# ProDocument_RFID-ARDUINO-FABLAB-BG_2024-.net
KiCad netlist of a schematic drawn in EasyEDA Pro
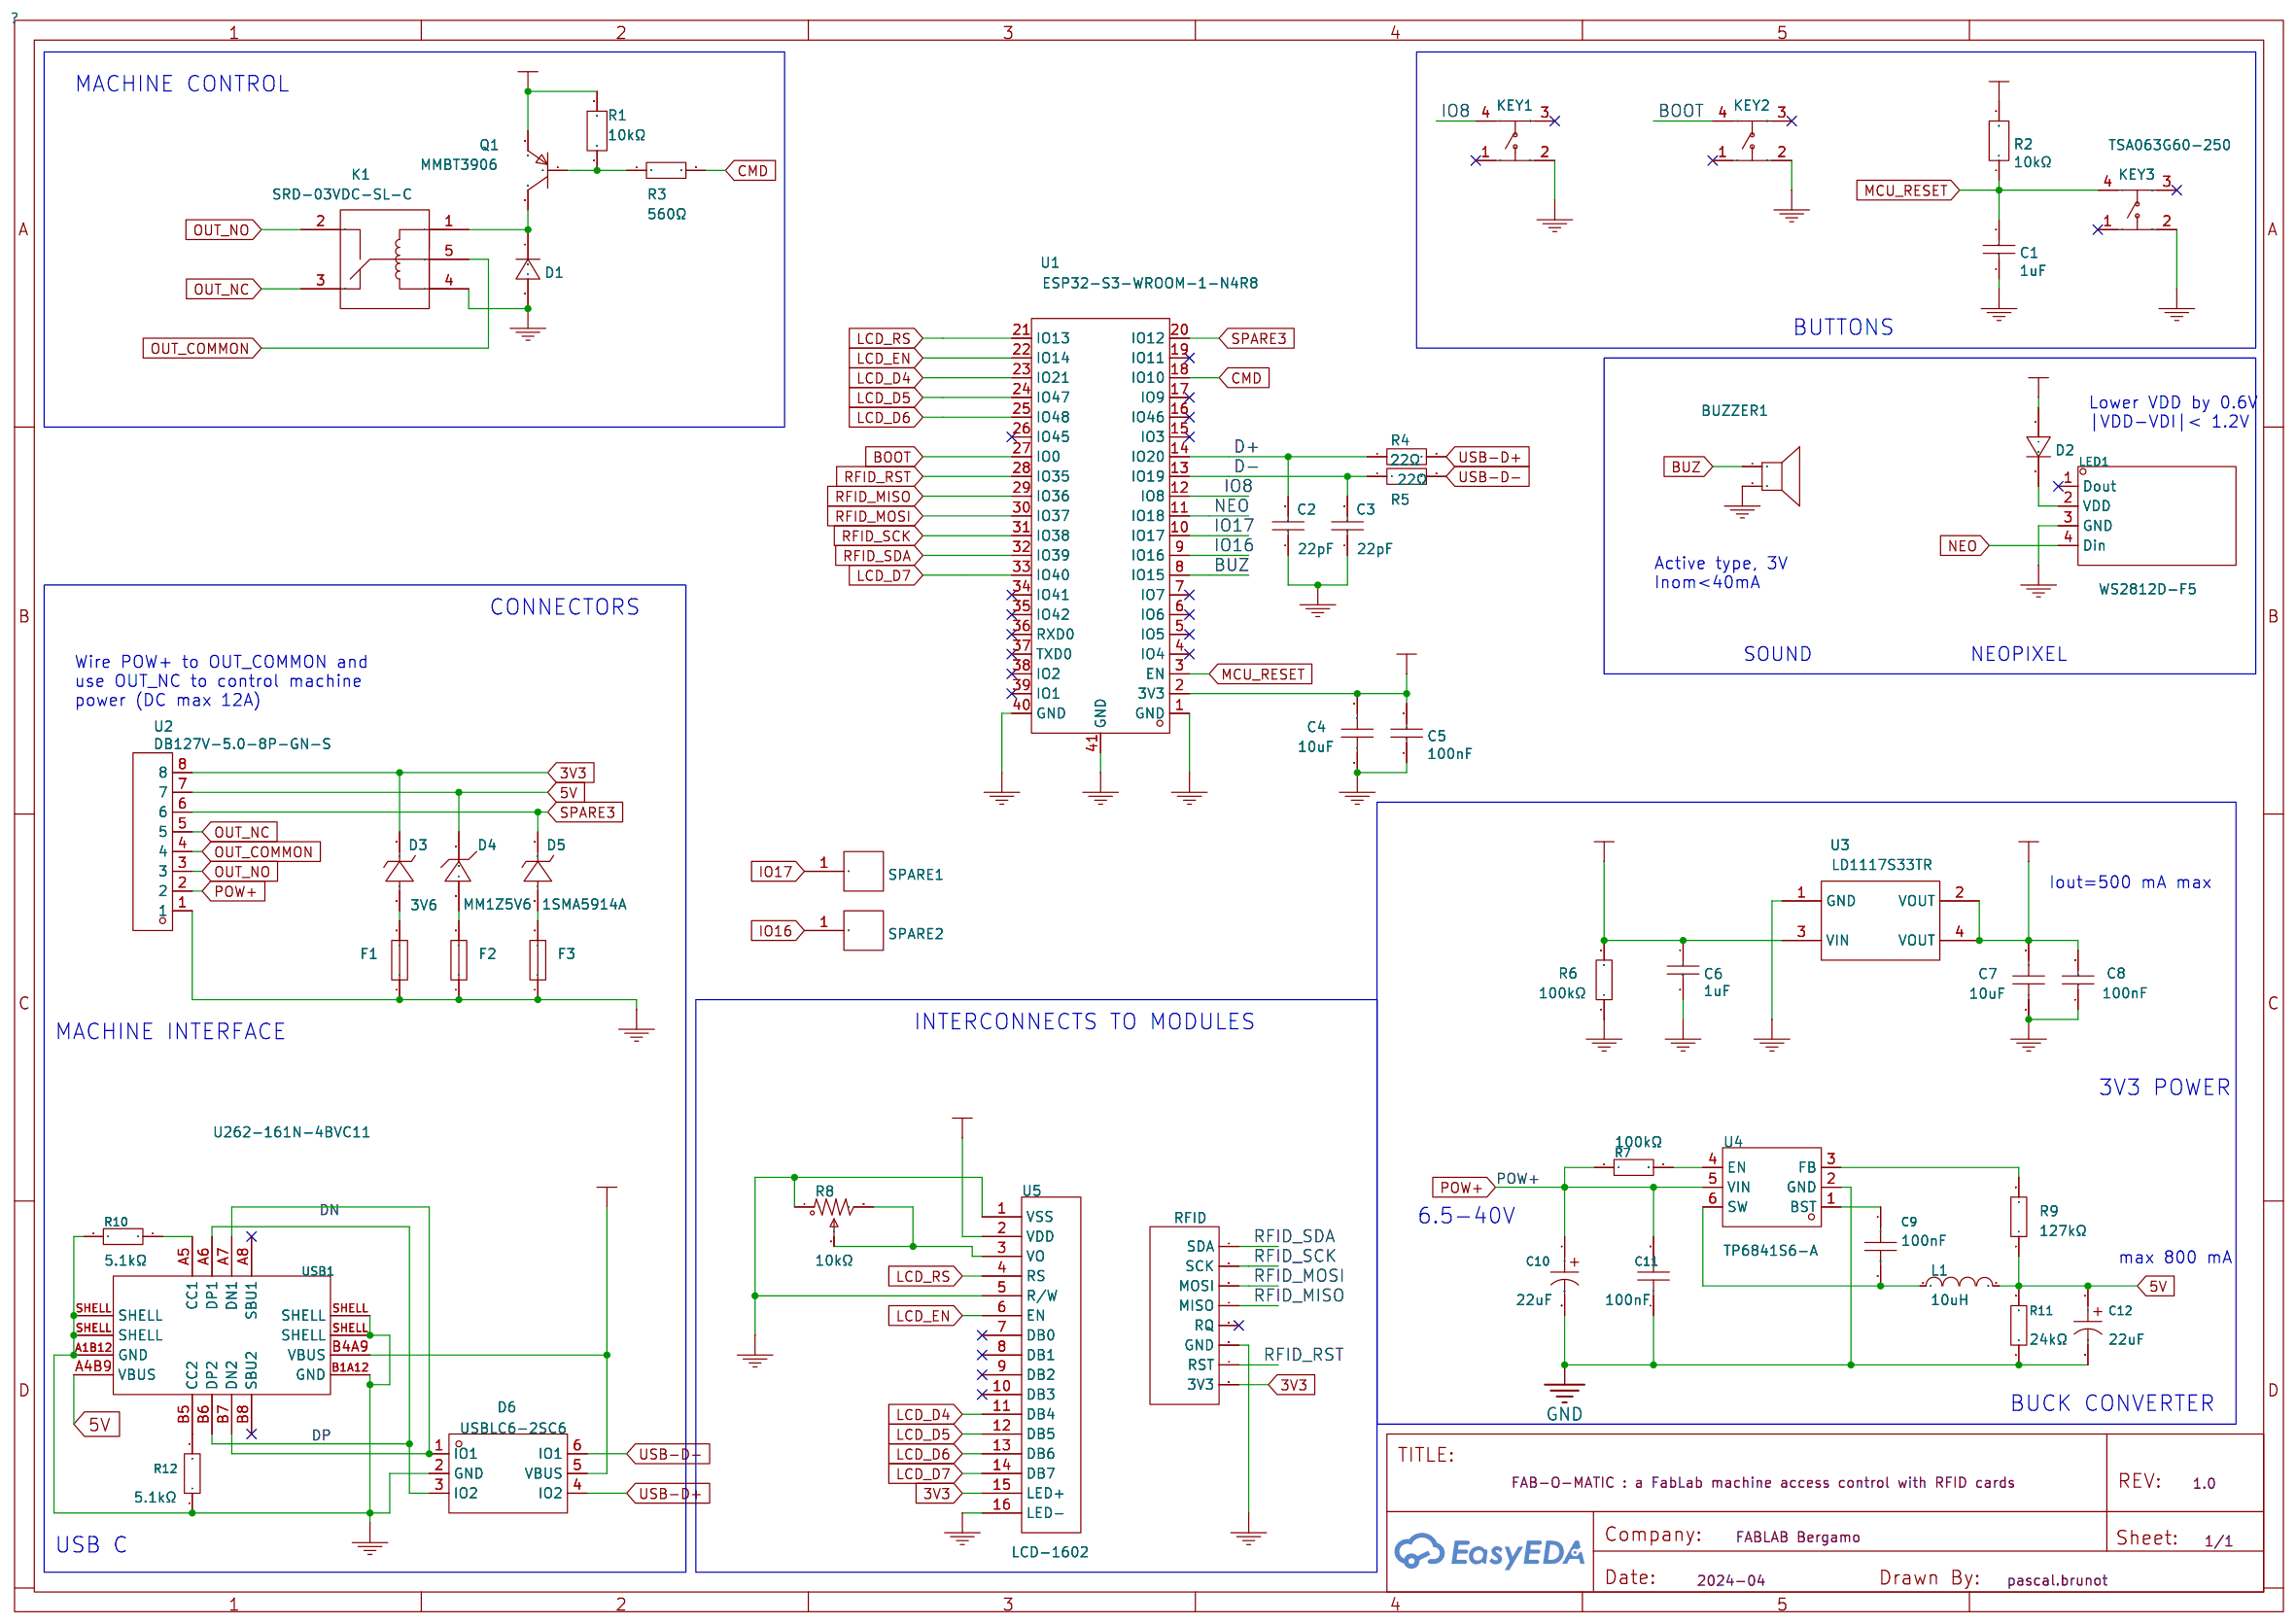
[diagram p0: schematic sheet]

(export (version "E")
  (design (tool "Eeschema 10.0.6"))
  (components
    (comp (ref "BUZZER1")
      (value "4kHz")
      (fields (field (name "Manufacturer Part") "SFN-12055PA6.5") (field (name "Manufacturer") "S&S(海旭)"))
      (libsource (lib "easyedapro") (part "4000Hz"))
    )
    (comp (ref "C1")
      (value "1uF")
      (fields
        (field (name "Manufacturer Part") "CL21B105KBFNNNE")
        (field (name "Manufacturer") "SAMSUNG(三星)")
      )
      (libsource (lib "easyedapro") (part "1uF"))
    )
    (comp (ref "C2")
      (value "22pF")
      (fields
        (field (name "Manufacturer Part") "CL10C220JB8NNNC")
        (field (name "Manufacturer") "SAMSUNG(三星)")
      )
      (libsource (lib "easyedapro") (part "22pF"))
    )
    (comp (ref "C3")
      (value "22pF")
      (fields
        (field (name "Manufacturer Part") "CL10C220JB8NNNC")
        (field (name "Manufacturer") "SAMSUNG(三星)")
      )
      (libsource (lib "easyedapro") (part "22pF"))
    )
    (comp (ref "C4")
      (value "10uF")
      (fields
        (field (name "Manufacturer Part") "GRM21BR61H106KE43L")
        (field (name "Manufacturer") "muRata(村田)")
      )
      (libsource (lib "easyedapro") (part "10uF"))
    )
    (comp (ref "C5")
      (value "100nF")
      (fields
        (field (name "Manufacturer Part") "CL21B104KCFNNNE")
        (field (name "Manufacturer") "SAMSUNG(三星)")
      )
      (libsource (lib "easyedapro") (part "100nF"))
    )
    (comp (ref "C6")
      (value "1uF")
      (fields
        (field (name "Manufacturer Part") "CL21B105KBFNNNE")
        (field (name "Manufacturer") "SAMSUNG(三星)")
      )
      (libsource (lib "easyedapro") (part "1uF"))
    )
    (comp (ref "C7")
      (value "10uF")
      (fields
        (field (name "Manufacturer Part") "GRM21BR61H106KE43L")
        (field (name "Manufacturer") "muRata(村田)")
      )
      (libsource (lib "easyedapro") (part "10uF"))
    )
    (comp (ref "C8")
      (value "100nF")
      (fields
        (field (name "Manufacturer Part") "CL21B104KCFNNNE")
        (field (name "Manufacturer") "SAMSUNG(三星)")
      )
      (libsource (lib "easyedapro") (part "100nF"))
    )
    (comp (ref "C9")
      (value "100nF")
      (footprint "easyedapro:C0603")
      (fields
        (field (name "Manufacturer Part") "CC0603KRX7R9BB104")
        (field (name "Manufacturer") "YAGEO(国巨)")
      )
      (libsource (lib "easyedapro") (part "CC0603KRX7R9BB104"))
    )
    (comp (ref "C10")
      (value "22uF")
      (footprint "easyedapro:CAP-SMD_BD6.3-L6.6-W6.6-FD")
      (fields
        (field (name "Manufacturer Part") "RVT22UF50V67RV0028")
        (field (name "Manufacturer") "KNSCHA(科尼盛)")
      )
      (libsource (lib "easyedapro") (part "RVT22UF50V67RV0028"))
    )
    (comp (ref "C11")
      (value "100nF")
      (footprint "easyedapro:C0603")
      (fields
        (field (name "Manufacturer Part") "CC0603KRX7R9BB104")
        (field (name "Manufacturer") "YAGEO(国巨)")
      )
      (libsource (lib "easyedapro") (part "CC0603KRX7R9BB104"))
    )
    (comp (ref "C12")
      (value "22uF")
      (footprint "easyedapro:CAP-SMD_BD6.3-L6.6-W6.6-FD")
      (fields
        (field (name "Manufacturer Part") "RVT22UF50V67RV0028")
        (field (name "Manufacturer") "KNSCHA(科尼盛)")
      )
      (libsource (lib "easyedapro") (part "RVT22UF50V67RV0028"))
    )
    (comp (ref "D1")
      (value "SM4007PL")
      (fields (field (name "Manufacturer") "MDD"))
      (libsource (lib "easyedapro") (part "SM4007PL"))
    )
    (comp (ref "D2")
      (value "SM4007PL")
      (fields (field (name "Manufacturer") "MDD"))
      (libsource (lib "easyedapro") (part "SM4007PL"))
    )
    (comp (ref "D3")
      (value "3V6")
      (fields (field (name "Manufacturer") "LGE(鲁光)"))
      (libsource (lib "easyedapro") (part "3V6"))
    )
    (comp (ref "D4")
      (value "MM1Z5V6")
      (fields (field (name "Manufacturer") "ST(先科)"))
      (libsource (lib "easyedapro") (part "5V6"))
    )
    (comp (ref "D5")
      (value "1SMA5914A")
      (fields (field (name "Manufacturer") "LGE(鲁光)"))
      (libsource (lib "easyedapro") (part "3V6"))
    )
    (comp (ref "D6")
      (value "USBLC6-2SC6")
      (fields (field (name "Manufacturer") "TECH PUBLIC(台舟)"))
      (libsource (lib "easyedapro") (part "USBLC6"))
    )
    (comp (ref "F1")
      (value "1206L016WR")
      (fields (field (name "Manufacturer") "Littelfuse(美国力特)"))
      (libsource (lib "easyedapro") (part "1206L016WR"))
    )
    (comp (ref "F2")
      (value "1206L016WR")
      (fields (field (name "Manufacturer") "Littelfuse(美国力特)"))
      (libsource (lib "easyedapro") (part "1206L016WR"))
    )
    (comp (ref "F3")
      (value "1206L016WR")
      (fields (field (name "Manufacturer") "Littelfuse(美国力特)"))
      (libsource (lib "easyedapro") (part "1206L016WR"))
    )
    (comp (ref "K1")
      (value "SRD-03VDC-SL-C")
      (fields (field (name "Manufacturer") "松乐"))
      (libsource (lib "easyedapro") (part "SRD-03VDC-SL-C_C496430"))
    )
    (comp (ref "KEY1")
      (value "TSA063G60-250")
      (footprint "easyedapro:KEY-SMD_4P-L6.1-W6.1-P4.50-LS9.0")
      (fields (field (name "Manufacturer") "BRIGHT(博瑞泰)"))
      (libsource (lib "easyedapro") (part "TSA063G60-250"))
    )
    (comp (ref "KEY2")
      (value "TSA063G60-250")
      (footprint "easyedapro:KEY-SMD_4P-L6.1-W6.1-P4.50-LS9.0")
      (fields (field (name "Manufacturer") "BRIGHT(博瑞泰)"))
      (libsource (lib "easyedapro") (part "TSA063G60-250"))
    )
    (comp (ref "KEY3")
      (value "TSA063G60-250")
      (footprint "easyedapro:KEY-SMD_4P-L6.1-W6.1-P4.50-LS9.0")
      (fields (field (name "Manufacturer") "BRIGHT(博瑞泰)"))
      (libsource (lib "easyedapro") (part "TSA063G60-250"))
    )
    (comp (ref "L1")
      (value "10uH")
      (footprint "easyedapro:IND-SMD_L4.0-W4.0")
      (fields (field (name "Manufacturer Part") "SWPA4030S100MT") (field (name "Manufacturer") "Sunlord(顺络)"))
      (libsource (lib "easyedapro") (part "SWPA4030S100MT"))
    )
    (comp (ref "LED1")
      (value "WS2812D-F5")
      (footprint "easyedapro:LED-TH_4P-BD5.8-P1.30")
      (description "Lamp Holder Type:5mm圆形灯头")
      (fields (field (name "Manufacturer") "worldsemi"))
      (libsource (lib "easyedapro") (part "WS2812D-F5"))
    )
    (comp (ref "P1")
      (value "RFID")
      (footprint "easyedapro:footprint_17af")
      (fields
        (field (name "Manufacturer Part") "Female headerHDR1X8-2.54")
        (field (name "Manufacturer") "BOOMELE")
      )
      (libsource (lib "easyedapro") (part "RFID"))
    )
    (comp (ref "Q1")
      (value "MMBT3906")
      (fields (field (name "Manufacturer") "High Diode(海德)"))
      (libsource (lib "easyedapro") (part "2N3906-AP"))
    )
    (comp (ref "R1")
      (value "10kΩ")
      (fields
        (field (name "Manufacturer Part") "0805W8F1002T5E")
        (field (name "Manufacturer") "UNI-ROYAL(厚声)")
      )
      (libsource (lib "easyedapro") (part "10k"))
    )
    (comp (ref "R2")
      (value "10kΩ")
      (fields
        (field (name "Manufacturer Part") "0805W8F1002T5E")
        (field (name "Manufacturer") "UNI-ROYAL(厚声)")
      )
      (libsource (lib "easyedapro") (part "10k"))
    )
    (comp (ref "R3")
      (value "560Ω")
      (fields
        (field (name "Manufacturer Part") "0805W8F5600T5E")
        (field (name "Manufacturer") "UNI-ROYAL(厚声)")
      )
      (libsource (lib "easyedapro") (part "560Ω"))
    )
    (comp (ref "R4")
      (value "22Ω")
      (fields
        (field (name "Manufacturer Part") "0603WAF220JT5E")
        (field (name "Manufacturer") "UNI-ROYAL(厚声)")
      )
      (libsource (lib "easyedapro") (part "22"))
    )
    (comp (ref "R5")
      (value "22Ω")
      (fields
        (field (name "Manufacturer Part") "0603WAF220JT5E")
        (field (name "Manufacturer") "UNI-ROYAL(厚声)")
      )
      (libsource (lib "easyedapro") (part "22"))
    )
    (comp (ref "R6")
      (value "100kΩ")
      (fields
        (field (name "Manufacturer Part") "0805W8F1003T5E")
        (field (name "Manufacturer") "UNI-ROYAL(厚声)")
      )
      (libsource (lib "easyedapro") (part "100kΩ"))
    )
    (comp (ref "R7")
      (value "100kΩ")
      (footprint "easyedapro:R0603")
      (fields
        (field (name "Manufacturer Part") "0603WAF1003T5E")
        (field (name "Manufacturer") "UNI-ROYAL(厚声)")
      )
      (libsource (lib "easyedapro") (part "0603WAF1003T5E"))
    )
    (comp (ref "R8")
      (value "10kΩ")
      (footprint "easyedapro:RES-ADJ-TH_3362P")
      (description "Resistance: Tolerance:±10% Tolerance:±10%")
      (fields (field (name "Manufacturer Part") "3362P-1-103") (field (name "Manufacturer") "BOCHEN(博晨)"))
      (libsource (lib "easyedapro") (part "3362P-1-103_C118956"))
    )
    (comp (ref "R9")
      (value "127kΩ")
      (footprint "easyedapro:R0603")
      (fields (field (name "Manufacturer Part") "RC0603FR-07127KL") (field (name "Manufacturer") "YAGEO(国巨)"))
      (libsource (lib "easyedapro") (part "RC0603FR-07127KL"))
    )
    (comp (ref "R10")
      (value "5.1kΩ")
      (footprint "easyedapro:R0603")
      (fields
        (field (name "Manufacturer Part") "0603WAF5101T5E")
        (field (name "Manufacturer") "UNI-ROYAL(厚声)")
      )
      (libsource (lib "easyedapro") (part "0603WAF5101T5E"))
    )
    (comp (ref "R11")
      (value "24kΩ")
      (footprint "easyedapro:R0603")
      (fields
        (field (name "Manufacturer Part") "0603WAF2402T5E")
        (field (name "Manufacturer") "UNI-ROYAL(厚声)")
      )
      (libsource (lib "easyedapro") (part "0603WAF2402T5E"))
    )
    (comp (ref "R12")
      (value "5.1kΩ")
      (footprint "easyedapro:R0603")
      (fields
        (field (name "Manufacturer Part") "0603WAF5101T5E")
        (field (name "Manufacturer") "UNI-ROYAL(厚声)")
      )
      (libsource (lib "easyedapro") (part "0603WAF5101T5E"))
    )
    (comp (ref "SPARE1")
      (value "0577-0-43-80-21-27-10-0")
      (footprint "easyedapro:footprint_662d")
      (libsource (lib "easyedapro") (part "0577-0-43-80-21-27-10-0"))
    )
    (comp (ref "SPARE2")
      (value "0577-0-43-80-21-27-10-0")
      (footprint "easyedapro:footprint_662d")
      (libsource (lib "easyedapro") (part "0577-0-43-80-21-27-10-0"))
    )
    (comp (ref "U1")
      (value "ESP32-S3-WROOM-1-N4R8")
      (fields (field (name "Manufacturer") "ESPRESSIF(乐鑫)"))
      (libsource (lib "easyedapro") (part "ESP32-S3-WROOM-1-N4"))
    )
    (comp (ref "U2")
      (value "DB127V-5.0-8P-GN-S")
      (fields (field (name "Manufacturer") "DORABO(地博电气)"))
      (libsource (lib "easyedapro") (part "DB127V-5.0-8P-GN-S"))
    )
    (comp (ref "U3")
      (value "LD1117S33TR")
      (fields (field (name "Manufacturer") "ST(意法半导体)"))
      (libsource (lib "easyedapro") (part "LD1117S33TR"))
    )
    (comp (ref "U4")
      (value "TP6841S6-A")
      (footprint "easyedapro:SOT-23-6_L2.9-W1.6-P0.95-LS2.8-BL")
      (fields (field (name "Manufacturer") "TECH PUBLIC(台舟)"))
      (libsource (lib "easyedapro") (part "TP6841S6-A"))
    )
    (comp (ref "U5")
      (value "LCD-1602")
      (footprint "easyedapro:footprint_8a57")
      (fields (field (name "Manufacturer Part") "?"))
      (libsource (lib "easyedapro") (part "LCD-1602"))
    )
    (comp (ref "USB1")
      (value "U262-161N-4BVC11")
      (footprint "easyedapro:USB-3.1-SMD_U262-161N-4BVC11")
      (fields (field (name "Manufacturer") "XKB Connectivity(中国星坤)"))
      (libsource (lib "easyedapro") (part "U262-16XN-4BVC11"))
    )
  )
  (nets
    (net (code "1") (name "/D+") (class "Default")
      (node (ref "C2") (pin "2") (pinfunction "2_2") (pintype "input"))
      (node (ref "R4") (pin "1") (pinfunction "1_1") (pintype "input"))
      (node (ref "U1") (pin "14") (pinfunction "IO20_14") (pintype "unspecified"))
    )
    (net (code "2") (name "/D-") (class "Default")
      (node (ref "C3") (pin "2") (pinfunction "2_2") (pintype "input"))
      (node (ref "R5") (pin "1") (pinfunction "1_1") (pintype "input"))
      (node (ref "U1") (pin "13") (pinfunction "IO19_13") (pintype "unspecified"))
    )
    (net (code "3") (name "/DN") (class "Default")
      (node (ref "D6") (pin "1") (pinfunction "IO1_1") (pintype "unspecified"))
      (node (ref "USB1") (pin "A7") (pinfunction "DN1_A7") (pintype "input"))
      (node (ref "USB1") (pin "B7") (pinfunction "DN2_B7") (pintype "input"))
    )
    (net (code "4") (name "/DP") (class "Default")
      (node (ref "D6") (pin "3") (pinfunction "IO2_3") (pintype "unspecified"))
      (node (ref "USB1") (pin "A6") (pinfunction "DP1_A6") (pintype "input"))
      (node (ref "USB1") (pin "B6") (pinfunction "DP2_B6") (pintype "input"))
    )
    (net (code "5") (name "/IO8") (class "Default")
      (node (ref "KEY1") (pin "4") (pinfunction "4_4") (pintype "input"))
      (node (ref "U1") (pin "12") (pinfunction "IO8_12") (pintype "unspecified"))
    )
    (net (code "6") (name "3V3") (class "Default")
      (node (ref "C4") (pin "2") (pinfunction "2_2") (pintype "unspecified"))
      (node (ref "C5") (pin "2") (pinfunction "2_2") (pintype "input"))
      (node (ref "C7") (pin "2") (pinfunction "2_2") (pintype "unspecified"))
      (node (ref "C8") (pin "2") (pinfunction "2_2") (pintype "input"))
      (node (ref "D3") (pin "1") (pinfunction "C_1") (pintype "unspecified"))
      (node (ref "P1") (pin "8") (pinfunction "3V3_8") (pintype "input"))
      (node (ref "Q1") (pin "1") (pinfunction "1_1") (pintype "input"))
      (node (ref "R1") (pin "2") (pinfunction "2_2") (pintype "unspecified"))
      (node (ref "R2") (pin "2") (pinfunction "2_2") (pintype "unspecified"))
      (node (ref "U1") (pin "2") (pinfunction "3V3_2") (pintype "unspecified"))
      (node (ref "U2") (pin "8") (pinfunction "8_8") (pintype "unspecified"))
      (node (ref "U3") (pin "2") (pinfunction "VOUT_2") (pintype "unspecified"))
      (node (ref "U3") (pin "4") (pinfunction "VOUT_4") (pintype "unspecified"))
      (node (ref "U5") (pin "15") (pinfunction "LED+_15") (pintype "unspecified"))
    )
    (net (code "7") (name "5V") (class "Default")
      (node (ref "C12") (pin "1") (pinfunction "1_1") (pintype "input"))
      (node (ref "C6") (pin "1") (pinfunction "1_1") (pintype "input"))
      (node (ref "D2") (pin "2") (pinfunction "A_2") (pintype "unspecified"))
      (node (ref "D4") (pin "1") (pinfunction "C_1") (pintype "unspecified"))
      (node (ref "D6") (pin "5") (pinfunction "VBUS_5") (pintype "unspecified"))
      (node (ref "L1") (pin "2") (pinfunction "2_2") (pintype "input"))
      (node (ref "R11") (pin "2") (pinfunction "2_2") (pintype "input"))
      (node (ref "R6") (pin "2") (pinfunction "2_2") (pintype "unspecified"))
      (node (ref "R9") (pin "1") (pinfunction "1_1") (pintype "unspecified"))
      (node (ref "U2") (pin "7") (pinfunction "7_7") (pintype "unspecified"))
      (node (ref "U3") (pin "3") (pinfunction "VIN_3") (pintype "unspecified"))
      (node (ref "U5") (pin "2") (pinfunction "VDD_2") (pintype "unspecified"))
      (node (ref "USB1") (pin "A4B9") (pinfunction "VBUS_A4B9") (pintype "input"))
      (node (ref "USB1") (pin "B4A9") (pinfunction "VBUS_B4A9") (pintype "input"))
    )
    (net (code "8") (name "BOOT") (class "Default")
      (node (ref "KEY2") (pin "4") (pinfunction "4_4") (pintype "input"))
      (node (ref "U1") (pin "27") (pinfunction "IO0_27") (pintype "unspecified"))
    )
    (net (code "9") (name "BUZ") (class "Default")
      (node (ref "BUZZER1") (pin "1") (pinfunction "1_1") (pintype "unspecified"))
      (node (ref "U1") (pin "8") (pinfunction "IO15_8") (pintype "unspecified"))
    )
    (net (code "10") (name "CMD") (class "Default")
      (node (ref "R3") (pin "2") (pinfunction "2_2") (pintype "input"))
      (node (ref "U1") (pin "18") (pinfunction "IO10_18") (pintype "unspecified"))
    )
    (net (code "11") (name "GND") (class "Default")
      (node (ref "BUZZER1") (pin "2") (pinfunction "2_2") (pintype "unspecified"))
      (node (ref "C1") (pin "1") (pinfunction "1_1") (pintype "input"))
      (node (ref "C10") (pin "2") (pinfunction "2_2") (pintype "input"))
      (node (ref "C11") (pin "1") (pinfunction "1_1") (pintype "input"))
      (node (ref "C12") (pin "2") (pinfunction "2_2") (pintype "input"))
      (node (ref "C2") (pin "1") (pinfunction "1_1") (pintype "input"))
      (node (ref "C3") (pin "1") (pinfunction "1_1") (pintype "input"))
      (node (ref "C4") (pin "1") (pinfunction "1_1") (pintype "unspecified"))
      (node (ref "C5") (pin "1") (pinfunction "1_1") (pintype "input"))
      (node (ref "C6") (pin "2") (pinfunction "2_2") (pintype "input"))
      (node (ref "C7") (pin "1") (pinfunction "1_1") (pintype "unspecified"))
      (node (ref "C8") (pin "1") (pinfunction "1_1") (pintype "input"))
      (node (ref "D1") (pin "2") (pinfunction "A_2") (pintype "unspecified"))
      (node (ref "D6") (pin "2") (pinfunction "GND_2") (pintype "unspecified"))
      (node (ref "F1") (pin "1") (pinfunction "1_1") (pintype "unspecified"))
      (node (ref "F2") (pin "1") (pinfunction "1_1") (pintype "unspecified"))
      (node (ref "F3") (pin "1") (pinfunction "1_1") (pintype "unspecified"))
      (node (ref "K1") (pin "4") (pinfunction "4_4") (pintype "unspecified"))
      (node (ref "KEY1") (pin "2") (pinfunction "2_2") (pintype "input"))
      (node (ref "KEY2") (pin "2") (pinfunction "2_2") (pintype "input"))
      (node (ref "KEY3") (pin "2") (pinfunction "2_2") (pintype "input"))
      (node (ref "LED1") (pin "3") (pinfunction "GND_3") (pintype "input"))
      (node (ref "P1") (pin "6") (pinfunction "GND_6") (pintype "input"))
      (node (ref "R10") (pin "2") (pinfunction "2_2") (pintype "input"))
      (node (ref "R11") (pin "1") (pinfunction "1_1") (pintype "input"))
      (node (ref "R12") (pin "1") (pinfunction "1_1") (pintype "input"))
      (node (ref "R6") (pin "1") (pinfunction "1_1") (pintype "unspecified"))
      (node (ref "R8") (pin "1") (pinfunction "1_1") (pintype "input"))
      (node (ref "U1") (pin "1") (pinfunction "GND_1") (pintype "unspecified"))
      (node (ref "U1") (pin "40") (pinfunction "GND_40") (pintype "unspecified"))
      (node (ref "U1") (pin "41") (pinfunction "GND_41") (pintype "unspecified"))
      (node (ref "U2") (pin "1") (pinfunction "1_1") (pintype "unspecified"))
      (node (ref "U3") (pin "1") (pinfunction "GND_1") (pintype "unspecified"))
      (node (ref "U4") (pin "2") (pinfunction "GND_2") (pintype "input"))
      (node (ref "U5") (pin "1") (pinfunction "VSS_1") (pintype "unspecified"))
      (node (ref "U5") (pin "16") (pinfunction "LED-_16") (pintype "unspecified"))
      (node (ref "U5") (pin "5") (pinfunction "R/W_5") (pintype "unspecified"))
      (node (ref "USB1") (pin "A1B12") (pinfunction "GND_A1B12") (pintype "input"))
      (node (ref "USB1") (pin "B1A12") (pinfunction "GND_B1A12") (pintype "input"))
      (node (ref "USB1") (pin "SHELL") (pinfunction "SHELL_SHELL") (pintype "input"))
    )
    (net (code "12") (name "IO16") (class "Default")
      (node (ref "SPARE2") (pin "1") (pinfunction "1_1") (pintype "unspecified"))
      (node (ref "U1") (pin "9") (pinfunction "IO16_9") (pintype "unspecified"))
    )
    (net (code "13") (name "IO17") (class "Default")
      (node (ref "SPARE1") (pin "1") (pinfunction "1_1") (pintype "unspecified"))
      (node (ref "U1") (pin "10") (pinfunction "IO17_10") (pintype "unspecified"))
    )
    (net (code "14") (name "LCD_D4") (class "Default")
      (node (ref "U1") (pin "23") (pinfunction "IO21_23") (pintype "unspecified"))
      (node (ref "U5") (pin "11") (pinfunction "DB4_11") (pintype "unspecified"))
    )
    (net (code "15") (name "LCD_D5") (class "Default")
      (node (ref "U1") (pin "24") (pinfunction "IO47_24") (pintype "unspecified"))
      (node (ref "U5") (pin "12") (pinfunction "DB5_12") (pintype "unspecified"))
    )
    (net (code "16") (name "LCD_D6") (class "Default")
      (node (ref "U1") (pin "25") (pinfunction "IO48_25") (pintype "unspecified"))
      (node (ref "U5") (pin "13") (pinfunction "DB6_13") (pintype "unspecified"))
    )
    (net (code "17") (name "LCD_D7") (class "Default")
      (node (ref "U1") (pin "33") (pinfunction "IO40_33") (pintype "unspecified"))
      (node (ref "U5") (pin "14") (pinfunction "DB7_14") (pintype "unspecified"))
    )
    (net (code "18") (name "LCD_EN") (class "Default")
      (node (ref "U1") (pin "22") (pinfunction "IO14_22") (pintype "unspecified"))
      (node (ref "U5") (pin "6") (pinfunction "EN_6") (pintype "unspecified"))
    )
    (net (code "19") (name "LCD_RS") (class "Default")
      (node (ref "U1") (pin "21") (pinfunction "IO13_21") (pintype "unspecified"))
      (node (ref "U5") (pin "4") (pinfunction "RS_4") (pintype "unspecified"))
    )
    (net (code "20") (name "MCU_RESET") (class "Default")
      (node (ref "C1") (pin "2") (pinfunction "2_2") (pintype "input"))
      (node (ref "KEY3") (pin "4") (pinfunction "4_4") (pintype "input"))
      (node (ref "R2") (pin "1") (pinfunction "1_1") (pintype "unspecified"))
      (node (ref "U1") (pin "3") (pinfunction "EN_3") (pintype "unspecified"))
    )
    (net (code "21") (name "NEO") (class "Default")
      (node (ref "LED1") (pin "4") (pinfunction "Din_4") (pintype "input"))
      (node (ref "U1") (pin "11") (pinfunction "IO18_11") (pintype "unspecified"))
    )
    (net (code "22") (name "Net-(D1-C)") (class "Default")
      (node (ref "D1") (pin "1") (pinfunction "C_1") (pintype "unspecified"))
      (node (ref "K1") (pin "1") (pinfunction "1_1") (pintype "unspecified"))
      (node (ref "Q1") (pin "3") (pinfunction "3_3") (pintype "input"))
    )
    (net (code "23") (name "Net-(D2-C)") (class "Default")
      (node (ref "D2") (pin "1") (pinfunction "C_1") (pintype "unspecified"))
      (node (ref "LED1") (pin "2") (pinfunction "VDD_2") (pintype "input"))
    )
    (net (code "24") (name "Net-(D3-A)") (class "Default")
      (node (ref "D3") (pin "2") (pinfunction "A_2") (pintype "unspecified"))
      (node (ref "F1") (pin "2") (pinfunction "2_2") (pintype "unspecified"))
    )
    (net (code "25") (name "Net-(D4-A)") (class "Default")
      (node (ref "D4") (pin "2") (pinfunction "A_2") (pintype "unspecified"))
      (node (ref "F2") (pin "2") (pinfunction "2_2") (pintype "unspecified"))
    )
    (net (code "26") (name "Net-(D5-A)") (class "Default")
      (node (ref "D5") (pin "2") (pinfunction "A_2") (pintype "unspecified"))
      (node (ref "F3") (pin "2") (pinfunction "2_2") (pintype "unspecified"))
    )
    (net (code "27") (name "Net-(Q1-Pad2)") (class "Default")
      (node (ref "Q1") (pin "2") (pinfunction "2_2") (pintype "input"))
      (node (ref "R1") (pin "1") (pinfunction "1_1") (pintype "unspecified"))
      (node (ref "R3") (pin "1") (pinfunction "1_1") (pintype "input"))
    )
    (net (code "28") (name "Net-(U4-BST)") (class "Default")
      (node (ref "C9") (pin "1") (pinfunction "1_1") (pintype "input"))
      (node (ref "U4") (pin "1") (pinfunction "BST_1") (pintype "input"))
    )
    (net (code "29") (name "Net-(U4-EN)") (class "Default")
      (node (ref "R7") (pin "2") (pinfunction "2_2") (pintype "input"))
      (node (ref "U4") (pin "4") (pinfunction "EN_4") (pintype "input"))
    )
    (net (code "30") (name "Net-(U4-FB)") (class "Default")
      (node (ref "R9") (pin "2") (pinfunction "2_2") (pintype "unspecified"))
      (node (ref "U4") (pin "3") (pinfunction "FB_3") (pintype "input"))
    )
    (net (code "31") (name "Net-(U4-SW)") (class "Default")
      (node (ref "C9") (pin "2") (pinfunction "2_2") (pintype "input"))
      (node (ref "L1") (pin "1") (pinfunction "1_1") (pintype "input"))
      (node (ref "U4") (pin "6") (pinfunction "SW_6") (pintype "input"))
    )
    (net (code "32") (name "Net-(U5-VO)") (class "Default")
      (node (ref "R8") (pin "2") (pinfunction "2_2") (pintype "input"))
      (node (ref "R8") (pin "3") (pinfunction "3_3") (pintype "input"))
      (node (ref "U5") (pin "3") (pinfunction "VO_3") (pintype "unspecified"))
    )
    (net (code "33") (name "Net-(USB1-CC1)") (class "Default")
      (node (ref "R10") (pin "1") (pinfunction "1_1") (pintype "input"))
      (node (ref "USB1") (pin "A5") (pinfunction "CC1_A5") (pintype "input"))
    )
    (net (code "34") (name "Net-(USB1-CC2)") (class "Default")
      (node (ref "R12") (pin "2") (pinfunction "2_2") (pintype "input"))
      (node (ref "USB1") (pin "B5") (pinfunction "CC2_B5") (pintype "input"))
    )
    (net (code "35") (name "OUT_COMMON") (class "Default")
      (node (ref "K1") (pin "5") (pinfunction "5_5") (pintype "unspecified"))
      (node (ref "U2") (pin "4") (pinfunction "4_4") (pintype "unspecified"))
    )
    (net (code "36") (name "OUT_NC") (class "Default")
      (node (ref "K1") (pin "3") (pinfunction "3_3") (pintype "unspecified"))
      (node (ref "U2") (pin "5") (pinfunction "5_5") (pintype "unspecified"))
    )
    (net (code "37") (name "OUT_NO") (class "Default")
      (node (ref "K1") (pin "2") (pinfunction "2_2") (pintype "unspecified"))
      (node (ref "U2") (pin "3") (pinfunction "3_3") (pintype "unspecified"))
    )
    (net (code "38") (name "POW+") (class "Default")
      (node (ref "C10") (pin "1") (pinfunction "1_1") (pintype "input"))
      (node (ref "C11") (pin "2") (pinfunction "2_2") (pintype "input"))
      (node (ref "R7") (pin "1") (pinfunction "1_1") (pintype "input"))
      (node (ref "U2") (pin "2") (pinfunction "2_2") (pintype "unspecified"))
      (node (ref "U4") (pin "5") (pinfunction "VIN_5") (pintype "input"))
    )
    (net (code "39") (name "RFID_MISO") (class "Default")
      (node (ref "P1") (pin "4") (pinfunction "MISO_4") (pintype "input"))
      (node (ref "U1") (pin "29") (pinfunction "IO36_29") (pintype "unspecified"))
    )
    (net (code "40") (name "RFID_MOSI") (class "Default")
      (node (ref "P1") (pin "3") (pinfunction "MOSI_3") (pintype "input"))
      (node (ref "U1") (pin "30") (pinfunction "IO37_30") (pintype "unspecified"))
    )
    (net (code "41") (name "RFID_RST") (class "Default")
      (node (ref "P1") (pin "7") (pinfunction "RST_7") (pintype "input"))
      (node (ref "U1") (pin "28") (pinfunction "IO35_28") (pintype "unspecified"))
    )
    (net (code "42") (name "RFID_SCK") (class "Default")
      (node (ref "P1") (pin "2") (pinfunction "SCK_2") (pintype "input"))
      (node (ref "U1") (pin "31") (pinfunction "IO38_31") (pintype "unspecified"))
    )
    (net (code "43") (name "RFID_SDA") (class "Default")
      (node (ref "P1") (pin "1") (pinfunction "SDA_1") (pintype "input"))
      (node (ref "U1") (pin "32") (pinfunction "IO39_32") (pintype "unspecified"))
    )
    (net (code "44") (name "SPARE3") (class "Default")
      (node (ref "D5") (pin "1") (pinfunction "C_1") (pintype "unspecified"))
      (node (ref "U1") (pin "20") (pinfunction "IO12_20") (pintype "unspecified"))
      (node (ref "U2") (pin "6") (pinfunction "6_6") (pintype "unspecified"))
    )
    (net (code "45") (name "USB-D+") (class "Default")
      (node (ref "D6") (pin "4") (pinfunction "IO2_4") (pintype "unspecified"))
      (node (ref "R4") (pin "2") (pinfunction "2_2") (pintype "input"))
    )
    (net (code "46") (name "USB-D-") (class "Default")
      (node (ref "D6") (pin "6") (pinfunction "IO1_6") (pintype "unspecified"))
      (node (ref "R5") (pin "2") (pinfunction "2_2") (pintype "input"))
    )
    (net (code "47") (name "unconnected-(KEY1-Pad1)") (class "Default")
      (node (ref "KEY1") (pin "1") (pinfunction "1_1") (pintype "input+no_connect"))
    )
    (net (code "48") (name "unconnected-(KEY1-Pad3)") (class "Default")
      (node (ref "KEY1") (pin "3") (pinfunction "3_3") (pintype "input+no_connect"))
    )
    (net (code "49") (name "unconnected-(KEY2-Pad1)") (class "Default")
      (node (ref "KEY2") (pin "1") (pinfunction "1_1") (pintype "input+no_connect"))
    )
    (net (code "50") (name "unconnected-(KEY2-Pad3)") (class "Default")
      (node (ref "KEY2") (pin "3") (pinfunction "3_3") (pintype "input+no_connect"))
    )
    (net (code "51") (name "unconnected-(KEY3-Pad1)") (class "Default")
      (node (ref "KEY3") (pin "1") (pinfunction "1_1") (pintype "input+no_connect"))
    )
    (net (code "52") (name "unconnected-(KEY3-Pad3)") (class "Default")
      (node (ref "KEY3") (pin "3") (pinfunction "3_3") (pintype "input+no_connect"))
    )
    (net (code "53") (name "unconnected-(LED1-Dout-Pad1)") (class "Default")
      (node (ref "LED1") (pin "1") (pinfunction "Dout_1") (pintype "input+no_connect"))
    )
    (net (code "54") (name "unconnected-(P1-RQ-Pad5)") (class "Default")
      (node (ref "P1") (pin "5") (pinfunction "RQ_5") (pintype "input+no_connect"))
    )
    (net (code "55") (name "unconnected-(U1-IO1-Pad39)") (class "Default")
      (node (ref "U1") (pin "39") (pinfunction "IO1_39") (pintype "unspecified+no_connect"))
    )
    (net (code "56") (name "unconnected-(U1-IO2-Pad38)") (class "Default")
      (node (ref "U1") (pin "38") (pinfunction "IO2_38") (pintype "unspecified+no_connect"))
    )
    (net (code "57") (name "unconnected-(U1-IO3-Pad15)") (class "Default")
      (node (ref "U1") (pin "15") (pinfunction "IO3_15") (pintype "unspecified+no_connect"))
    )
    (net (code "58") (name "unconnected-(U1-IO4-Pad4)") (class "Default")
      (node (ref "U1") (pin "4") (pinfunction "IO4_4") (pintype "unspecified+no_connect"))
    )
    (net (code "59") (name "unconnected-(U1-IO5-Pad5)") (class "Default")
      (node (ref "U1") (pin "5") (pinfunction "IO5_5") (pintype "unspecified+no_connect"))
    )
    (net (code "60") (name "unconnected-(U1-IO6-Pad6)") (class "Default")
      (node (ref "U1") (pin "6") (pinfunction "IO6_6") (pintype "unspecified+no_connect"))
    )
    (net (code "61") (name "unconnected-(U1-IO7-Pad7)") (class "Default")
      (node (ref "U1") (pin "7") (pinfunction "IO7_7") (pintype "unspecified+no_connect"))
    )
    (net (code "62") (name "unconnected-(U1-IO9-Pad17)") (class "Default")
      (node (ref "U1") (pin "17") (pinfunction "IO9_17") (pintype "unspecified+no_connect"))
    )
    (net (code "63") (name "unconnected-(U1-IO11-Pad19)") (class "Default")
      (node (ref "U1") (pin "19") (pinfunction "IO11_19") (pintype "unspecified+no_connect"))
    )
    (net (code "64") (name "unconnected-(U1-IO41-Pad34)") (class "Default")
      (node (ref "U1") (pin "34") (pinfunction "IO41_34") (pintype "unspecified+no_connect"))
    )
    (net (code "65") (name "unconnected-(U1-IO42-Pad35)") (class "Default")
      (node (ref "U1") (pin "35") (pinfunction "IO42_35") (pintype "unspecified+no_connect"))
    )
    (net (code "66") (name "unconnected-(U1-IO45-Pad26)") (class "Default")
      (node (ref "U1") (pin "26") (pinfunction "IO45_26") (pintype "unspecified+no_connect"))
    )
    (net (code "67") (name "unconnected-(U1-IO46-Pad16)") (class "Default")
      (node (ref "U1") (pin "16") (pinfunction "IO46_16") (pintype "unspecified+no_connect"))
    )
    (net (code "68") (name "unconnected-(U1-RXD0-Pad36)") (class "Default")
      (node (ref "U1") (pin "36") (pinfunction "RXD0_36") (pintype "unspecified+no_connect"))
    )
    (net (code "69") (name "unconnected-(U1-TXD0-Pad37)") (class "Default")
      (node (ref "U1") (pin "37") (pinfunction "TXD0_37") (pintype "unspecified+no_connect"))
    )
    (net (code "70") (name "unconnected-(U5-DB0-Pad7)") (class "Default")
      (node (ref "U5") (pin "7") (pinfunction "DB0_7") (pintype "unspecified+no_connect"))
    )
    (net (code "71") (name "unconnected-(U5-DB1-Pad8)") (class "Default")
      (node (ref "U5") (pin "8") (pinfunction "DB1_8") (pintype "unspecified+no_connect"))
    )
    (net (code "72") (name "unconnected-(U5-DB2-Pad9)") (class "Default")
      (node (ref "U5") (pin "9") (pinfunction "DB2_9") (pintype "unspecified+no_connect"))
    )
    (net (code "73") (name "unconnected-(U5-DB3-Pad10)") (class "Default")
      (node (ref "U5") (pin "10") (pinfunction "DB3_10") (pintype "unspecified+no_connect"))
    )
    (net (code "74") (name "unconnected-(USB1-SBU1-PadA8)") (class "Default")
      (node (ref "USB1") (pin "A8") (pinfunction "SBU1_A8") (pintype "input+no_connect"))
    )
    (net (code "75") (name "unconnected-(USB1-SBU2-PadB8)") (class "Default")
      (node (ref "USB1") (pin "B8") (pinfunction "SBU2_B8") (pintype "input+no_connect"))
    )
  )
)
